# STM32F413CG_WM8731.net
KiCad netlist of a schematic drawn in EAGLE
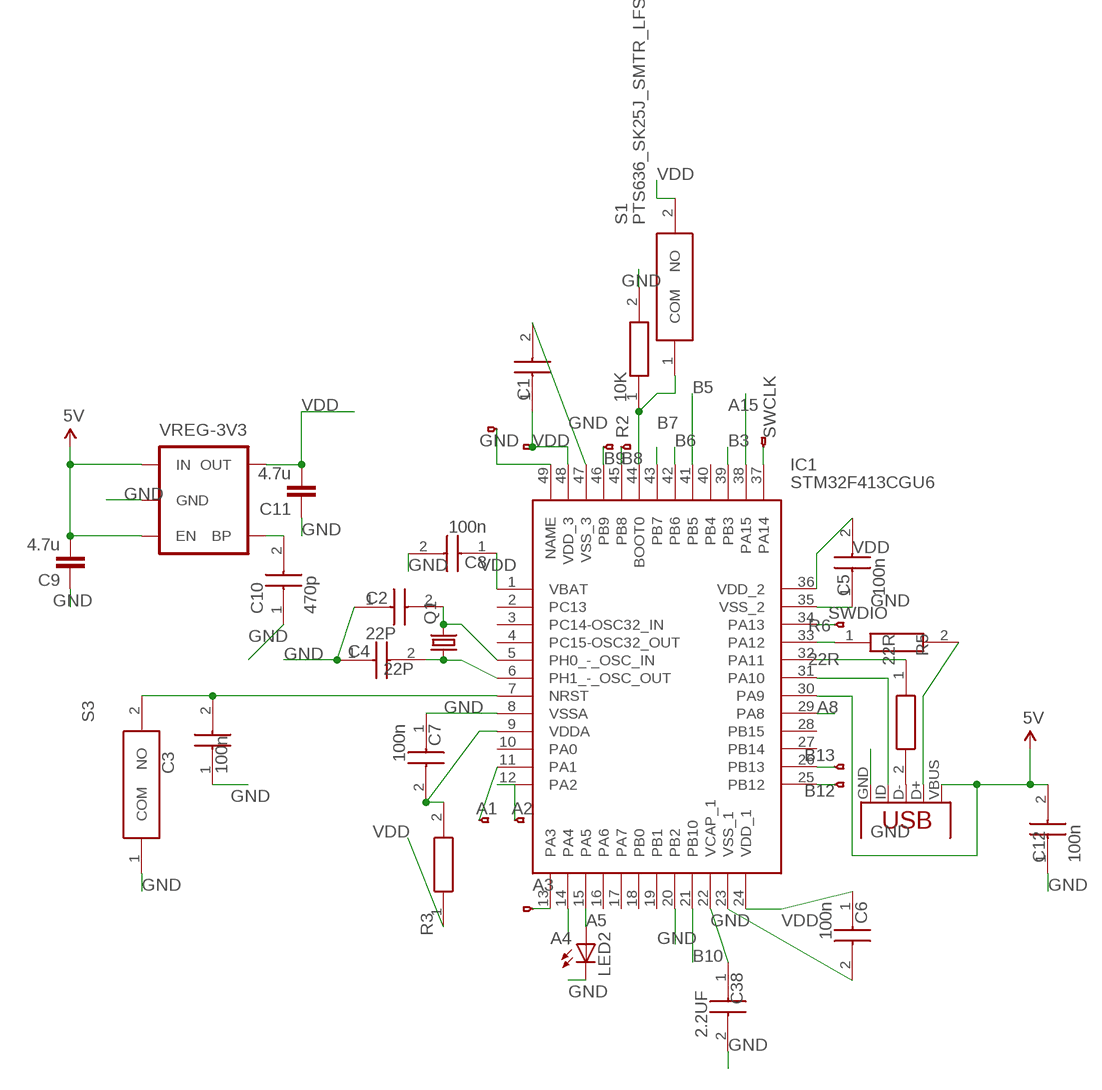
[diagram p0: schematic, sheet 1]
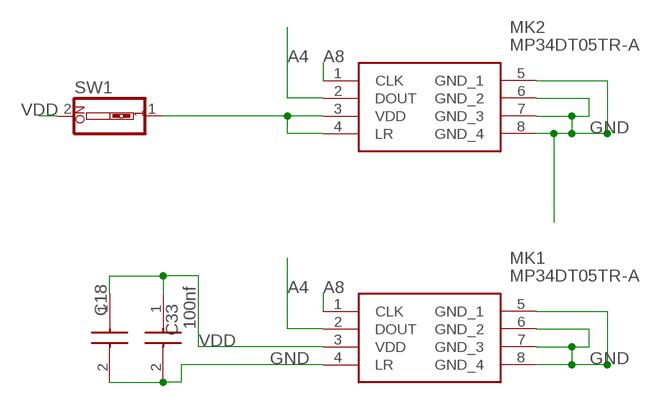
[diagram p1: schematic, sheet 2]
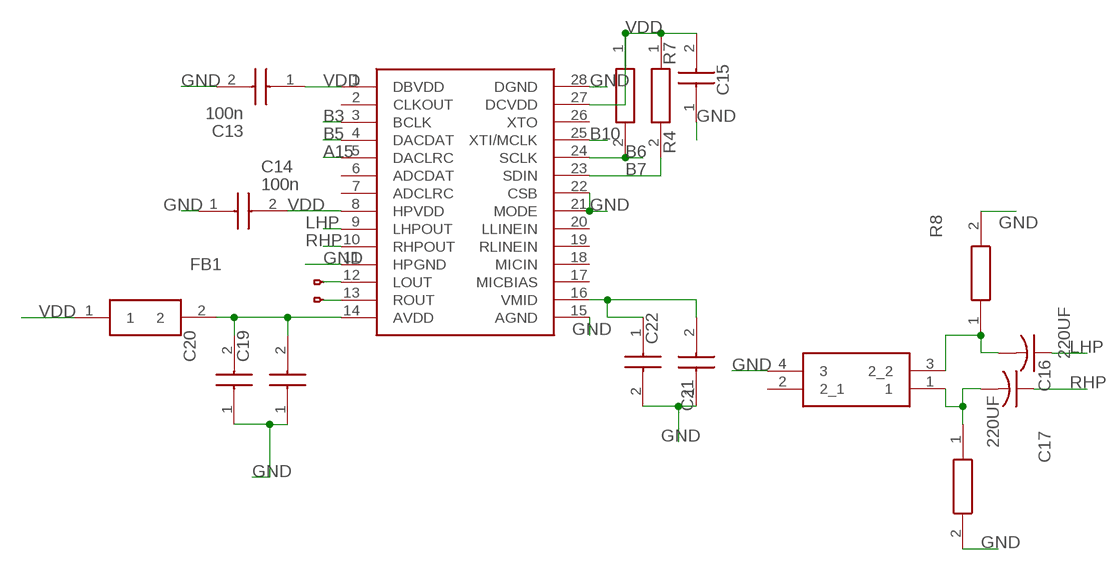
[diagram p2: schematic, sheet 3]

(export (version "E")
  (design (tool "Eeschema 10.0.6"))
  (components
    (comp (ref "C13")
      (value "100n")
      (footprint "eagle-import:CAPC1608X95N")
      (fields
        (field (name "MANUFACTURER_PART_NUMBER") "C0603C104M4RAC7411")
        (field (name "MOUSER_PART_NUMBER") "80-C0603C104M4R7411")
      )
      (libsource (lib "eagle-import") (part "C0603C104M4RAC7411"))
    )
    (comp (ref "C14")
      (value "100n")
      (footprint "eagle-import:CAPC1608X95N")
      (fields
        (field (name "MANUFACTURER_PART_NUMBER") "C0603C104M4RAC7411")
        (field (name "MOUSER_PART_NUMBER") "80-C0603C104M4R7411")
      )
      (libsource (lib "eagle-import") (part "C0603C104M4RAC7411"))
    )
    (comp (ref "C15")
      (value "C0603C104M4RAC7411")
      (footprint "eagle-import:CAPC1608X95N")
      (fields (field (name "MOUSER_PART_NUMBER") "80-C0603C104M4R7411"))
      (libsource (lib "eagle-import") (part "C0603C104M4RAC7411"))
    )
    (comp (ref "C16")
      (value "220UF")
      (footprint "eagle-import:C025-024X044")
      (libsource (lib "eagle-import") (part "C-US025-024X044"))
    )
    (comp (ref "C17")
      (value "220UF")
      (footprint "eagle-import:C025-024X044")
      (libsource (lib "eagle-import") (part "C-US025-024X044"))
    )
    (comp (ref "C19")
      (value "C0603C104M4RAC7411")
      (footprint "eagle-import:CAPC1608X95N")
      (fields (field (name "MOUSER_PART_NUMBER") "80-C0603C104M4R7411"))
      (libsource (lib "eagle-import") (part "C0603C104M4RAC7411_100nF_C0603C104M4RAC7411"))
    )
    (comp (ref "C20")
      (value "CL21A106KAYNNNE_10UF")
      (footprint "eagle-import:CAPC2012X145N")
      (fields (field (name "MANUFACTURER_PART_NUMBER") "CL21A106KAYNNNE"))
      (libsource (lib "eagle-import") (part "CL21A106KAYNNNE"))
    )
    (comp (ref "C21")
      (value "CL21A106KAYNNNE")
      (footprint "eagle-import:CAPC2012X145N")
      (libsource (lib "eagle-import") (part "CL21A106KAYNNNE"))
    )
    (comp (ref "C22")
      (value "C0603C104M4RAC7411")
      (footprint "eagle-import:CAPC1608X95N")
      (fields (field (name "MOUSER_PART_NUMBER") "80-C0603C104M4R7411"))
      (libsource (lib "eagle-import") (part "C0603C104M4RAC7411_100nF_C0603C104M4RAC7411"))
    )
    (comp (ref "FB1")
      (value "BLM18BD252SN1D")
      (footprint "eagle-import:BEADC1608X95N")
      (fields
        (field (name "MOUSER_PART_NUMBER") "81-BLM18BD252SN1D")
        (field (name "RS_PART_NUMBER") "7241321P")
      )
      (libsource (lib "eagle-import") (part "BLM18BD252SN1D"))
    )
    (comp (ref "IC2")
      (value "WM8731SEDS_RV")
      (footprint "eagle-import:SOP65P780X200-28N")
      (fields (field (name "MANUFACTURER_PART_NUMBER") "WM8731SEDS/RV"))
      (libsource (lib "eagle-import") (part "WM8731SEDS_RV"))
    )
    (comp (ref "J2")
      (value "1503_02")
      (footprint "eagle-import:150302")
      (fields (field (name "MANUFACTURER_PART_NUMBER") "1503 02"))
      (libsource (lib "eagle-import") (part "1503_02"))
    )
    (comp (ref "JP12")
      (value "HEADERHOLE-HEADERHOLE")
      (footprint "eagle-import:1X1-HEADER-HOLE")
      (libsource (lib "eagle-import") (part "HEADERHOLE-HEADERHOLE"))
    )
    (comp (ref "JP13")
      (value "HEADERHOLE-HEADERHOLE")
      (footprint "eagle-import:1X1-HEADER-HOLE")
      (libsource (lib "eagle-import") (part "HEADERHOLE-HEADERHOLE"))
    )
    (comp (ref "R4")
      (value "CR0603-JW-472ELF")
      (footprint "eagle-import:RESC1608X55N")
      (fields
        (field (name "MOUSER_PART_NUMBER") "652-CR0603-JW-472ELF")
        (field (name "RS_PART_NUMBER") "7408956P")
      )
      (libsource (lib "eagle-import") (part "CR0603-JW-472ELF"))
    )
    (comp (ref "R7")
      (value "CR0603-JW-472ELF")
      (footprint "eagle-import:RESC1608X55N")
      (fields
        (field (name "MOUSER_PART_NUMBER") "652-CR0603-JW-472ELF")
        (field (name "RS_PART_NUMBER") "7408956P")
      )
      (libsource (lib "eagle-import") (part "CR0603-JW-472ELF"))
    )
    (comp (ref "R8")
      (value "CR0603-JW-472ELF")
      (footprint "eagle-import:RESC1608X55N")
      (fields
        (field (name "MOUSER_PART_NUMBER") "652-CR0603-JW-472ELF")
        (field (name "RS_PART_NUMBER") "7408956P")
      )
      (libsource (lib "eagle-import") (part "CR0603-JW-472ELF"))
    )
    (comp (ref "R9")
      (value "CR0603-JW-472ELF")
      (footprint "eagle-import:RESC1608X55N")
      (fields
        (field (name "MOUSER_PART_NUMBER") "652-CR0603-JW-472ELF")
        (field (name "RS_PART_NUMBER") "7408956P")
      )
      (libsource (lib "eagle-import") (part "CR0603-JW-472ELF"))
    )
    (comp (ref "C1")
      (value "C0603C104M4RAC7411")
      (footprint "eagle-import:CAPC1608X95N")
      (fields (field (name "MOUSER_PART_NUMBER") "80-C0603C104M4R7411"))
      (libsource (lib "eagle-import") (part "C0603C104M4RAC7411"))
    )
    (comp (ref "C2")
      (value "22P")
      (footprint "eagle-import:CAPC1608X80N")
      (fields
        (field (name "MANUFACTURER_PART_NUMBER") "C1608C0G1H150J080AA")
        (field (name "MOUSER_PART_NUMBER") "810-C1608C0G1H150J")
        (field (name "RS_PART_NUMBER") "7882935")
      )
      (libsource (lib "eagle-import") (part "C1608C0G1H150J080AA"))
    )
    (comp (ref "C3")
      (value "100n")
      (footprint "eagle-import:CAPC1608X95N")
      (fields
        (field (name "MANUFACTURER_PART_NUMBER") "C0603C104M4RAC7411")
        (field (name "MOUSER_PART_NUMBER") "80-C0603C104M4R7411")
      )
      (libsource (lib "eagle-import") (part "C0603C104M4RAC7411"))
    )
    (comp (ref "C4")
      (value "22P")
      (footprint "eagle-import:CAPC1608X80N")
      (fields
        (field (name "MANUFACTURER_PART_NUMBER") "C1608C0G1H150J080AA")
        (field (name "MOUSER_PART_NUMBER") "810-C1608C0G1H150J")
        (field (name "RS_PART_NUMBER") "7882935")
      )
      (libsource (lib "eagle-import") (part "C1608C0G1H150J080AA"))
    )
    (comp (ref "C5")
      (value "100n")
      (footprint "eagle-import:CAPC1608X95N")
      (fields
        (field (name "MANUFACTURER_PART_NUMBER") "C0603C104M4RAC7411")
        (field (name "MOUSER_PART_NUMBER") "80-C0603C104M4R7411")
      )
      (libsource (lib "eagle-import") (part "C0603C104M4RAC7411"))
    )
    (comp (ref "C6")
      (value "100n")
      (footprint "eagle-import:CAPC1608X95N")
      (fields
        (field (name "MANUFACTURER_PART_NUMBER") "C0603C104M4RAC7411")
        (field (name "MOUSER_PART_NUMBER") "80-C0603C104M4R7411")
      )
      (libsource (lib "eagle-import") (part "C0603C104M4RAC7411"))
    )
    (comp (ref "C7")
      (value "100n")
      (footprint "eagle-import:CAPC1608X95N")
      (fields
        (field (name "MANUFACTURER_PART_NUMBER") "C0603C104M4RAC7411")
        (field (name "MOUSER_PART_NUMBER") "80-C0603C104M4R7411")
      )
      (libsource (lib "eagle-import") (part "C0603C104M4RAC7411"))
    )
    (comp (ref "C8")
      (value "100n")
      (footprint "eagle-import:CAPC1608X95N")
      (fields
        (field (name "MANUFACTURER_PART_NUMBER") "C0603C104M4RAC7411")
        (field (name "MOUSER_PART_NUMBER") "80-C0603C104M4R7411")
      )
      (libsource (lib "eagle-import") (part "C0603C104M4RAC7411"))
    )
    (comp (ref "C9")
      (value "4.7u")
      (footprint "eagle-import:C2.5-3")
      (libsource (lib "eagle-import") (part "C2,5-3"))
    )
    (comp (ref "C10")
      (value "470p")
      (footprint "eagle-import:CAPC1608X87N")
      (fields
        (field (name "MANUFACTURER_PART_NUMBER") "C0603C471K3RACTU")
        (field (name "MOUSER_PART_NUMBER") "80-C0603C471K3R")
      )
      (libsource (lib "eagle-import") (part "C0603C471K3RACTU"))
    )
    (comp (ref "C11")
      (value "4.7u")
      (footprint "eagle-import:C2.5-3")
      (libsource (lib "eagle-import") (part "C2,5-3"))
    )
    (comp (ref "C12")
      (value "100n")
      (footprint "eagle-import:CAPC1608X95N")
      (fields
        (field (name "MANUFACTURER_PART_NUMBER") "C0603C104M4RAC7411")
        (field (name "MOUSER_PART_NUMBER") "80-C0603C104M4R7411")
      )
      (libsource (lib "eagle-import") (part "C0603C104M4RAC7411"))
    )
    (comp (ref "C38")
      (value "2.2UF")
      (footprint "eagle-import:CAPC2012X145N")
      (fields
        (field (name "MANUFACTURER_PART_NUMBER") "C2012X7R1E225K125AB")
        (field (name "MOUSER_PART_NUMBER") "810-C2012X7R1E225K")
        (field (name "RS_PART_NUMBER") "9159394P")
      )
      (libsource (lib "eagle-import") (part "C2012X7R1E225K125AB"))
    )
    (comp (ref "IC1")
      (value "STM32F413CGU6")
      (footprint "eagle-import:QFN50P700X700X60-49N")
      (fields (field (name "MOUSER_PART_NUMBER") "511-STM32F413CGU6"))
      (libsource (lib "eagle-import") (part "STM32F413CGU6"))
    )
    (comp (ref "JP1")
      (value "HEADERHOLE-HEADERHOLE")
      (footprint "eagle-import:1X1-HEADER-HOLE")
      (libsource (lib "eagle-import") (part "HEADERHOLE-HEADERHOLE"))
    )
    (comp (ref "JP2")
      (value "HEADERHOLE-HEADERHOLE")
      (footprint "eagle-import:1X1-HEADER-HOLE")
      (libsource (lib "eagle-import") (part "HEADERHOLE-HEADERHOLE"))
    )
    (comp (ref "JP3")
      (value "HEADERHOLE-HEADERHOLE")
      (footprint "eagle-import:1X1-HEADER-HOLE")
      (libsource (lib "eagle-import") (part "HEADERHOLE-HEADERHOLE"))
    )
    (comp (ref "JP4")
      (value "HEADERHOLE-HEADERHOLE")
      (footprint "eagle-import:1X1-HEADER-HOLE")
      (libsource (lib "eagle-import") (part "HEADERHOLE-HEADERHOLE"))
    )
    (comp (ref "JP5")
      (value "HEADERHOLE-HEADERHOLE")
      (footprint "eagle-import:1X1-HEADER-HOLE")
      (libsource (lib "eagle-import") (part "HEADERHOLE-HEADERHOLE"))
    )
    (comp (ref "JP6")
      (value "HEADERHOLE-HEADERHOLE")
      (footprint "eagle-import:1X1-HEADER-HOLE")
      (libsource (lib "eagle-import") (part "HEADERHOLE-HEADERHOLE"))
    )
    (comp (ref "JP7")
      (value "HEADERHOLE-HEADERHOLE")
      (footprint "eagle-import:1X1-HEADER-HOLE")
      (libsource (lib "eagle-import") (part "HEADERHOLE-HEADERHOLE"))
    )
    (comp (ref "JP8")
      (value "HEADERHOLE-HEADERHOLE")
      (footprint "eagle-import:1X1-HEADER-HOLE")
      (libsource (lib "eagle-import") (part "HEADERHOLE-HEADERHOLE"))
    )
    (comp (ref "JP9")
      (value "HEADERHOLE-HEADERHOLE")
      (footprint "eagle-import:1X1-HEADER-HOLE")
      (libsource (lib "eagle-import") (part "HEADERHOLE-HEADERHOLE"))
    )
    (comp (ref "JP10")
      (value "HEADERHOLE-HEADERHOLE")
      (footprint "eagle-import:1X1-HEADER-HOLE")
      (libsource (lib "eagle-import") (part "HEADERHOLE-HEADERHOLE"))
    )
    (comp (ref "JP11")
      (value "HEADERHOLE-HEADERHOLE")
      (footprint "eagle-import:1X1-HEADER-HOLE")
      (libsource (lib "eagle-import") (part "HEADERHOLE-HEADERHOLE"))
    )
    (comp (ref "LED2")
      (value "LED0603")
      (footprint "eagle-import:LED-0603")
      (libsource (lib "eagle-import") (part "LED0603"))
    )
    (comp (ref "Q1")
      (value "CRYSTALHC49S")
      (footprint "eagle-import:HC49_S")
      (libsource (lib "eagle-import") (part "CRYSTALHC49S"))
    )
    (comp (ref "R2")
      (value "10K")
      (footprint "eagle-import:RESC1005X40N")
      (fields
        (field (name "MANUFACTURER_PART_NUMBER") "CRCW040210K0JNED")
        (field (name "MOUSER_PART_NUMBER") "71-CRCW0402J-10K-E3")
      )
      (libsource (lib "eagle-import") (part "CRCW040210K0JNED"))
    )
    (comp (ref "R3")
      (value "CRCW040222R0FKED")
      (footprint "eagle-import:RESC1005X40N")
      (fields
        (field (name "MOUSER_PART_NUMBER") "71-CRCW0402-22-E3")
        (field (name "RS_PART_NUMBER") "6788983P")
      )
      (libsource (lib "eagle-import") (part "CRCW040222R0FKED"))
    )
    (comp (ref "R5")
      (value "22R")
      (footprint "eagle-import:RESC1005X40N")
      (fields
        (field (name "MANUFACTURER_PART_NUMBER") "CRCW040222R0FKED")
        (field (name "MOUSER_PART_NUMBER") "71-CRCW0402-22-E3")
        (field (name "RS_PART_NUMBER") "6788983P")
      )
      (libsource (lib "eagle-import") (part "CRCW040222R0FKED"))
    )
    (comp (ref "R6")
      (value "22R")
      (footprint "eagle-import:RESC1005X40N")
      (fields
        (field (name "MANUFACTURER_PART_NUMBER") "CRCW040222R0FKED")
        (field (name "MOUSER_PART_NUMBER") "71-CRCW0402-22-E3")
        (field (name "RS_PART_NUMBER") "6788983P")
      )
      (libsource (lib "eagle-import") (part "CRCW040222R0FKED"))
    )
    (comp (ref "S1")
      (value "PTS636_SK25J_SMTR_LFS")
      (footprint "eagle-import:PTS636SK25JSMTRLFS")
      (fields
        (field (name "MANUFACTURER_PART_NUMBER") "PTS636 SK25J SMTR LFS")
        (field (name "MOUSER_PART_NUMBER") "611-PTS636SK25JSMTRL")
      )
      (libsource (lib "eagle-import") (part "PTS636_SK25J_SMTR_LFS"))
    )
    (comp (ref "S3")
      (value "PTS636_SK25J_SMTR_LFS")
      (footprint "eagle-import:PTS636SK25JSMTRLFS")
      (fields
        (field (name "MANUFACTURER_PART_NUMBER") "PTS636 SK25J SMTR LFS")
        (field (name "MOUSER_PART_NUMBER") "611-PTS636SK25JSMTRL")
      )
      (libsource (lib "eagle-import") (part "PTS636_SK25J_SMTR_LFS"))
    )
    (comp (ref "VREG-3V3")
      (value "V_REG_LDOSMD")
      (footprint "eagle-import:SOT23-5")
      (libsource (lib "eagle-import") (part "V_REG_LDOSMD"))
    )
    (comp (ref "X1")
      (value "USB-MICROB-SMD")
      (footprint "eagle-import:USB-MICROB-SMD")
      (libsource (lib "eagle-import") (part "USB-MICROB-SMD"))
    )
    (comp (ref "C18")
      (value "1UF")
      (footprint "eagle-import:CAPC1005X55N")
      (fields
        (field (name "MANUFACTURER_PART_NUMBER") "CC0402KRX5R6BB105")
        (field (name "MOUSER_PART_NUMBER") "603-CC402KRX5R6BB105")
      )
      (libsource (lib "eagle-import") (part "CC0402KRX5R6BB105"))
    )
    (comp (ref "C33")
      (value "100nf")
      (footprint "eagle-import:CAPC1608X95N")
      (fields
        (field (name "MANUFACTURER_PART_NUMBER") "C0603C104M4RAC7411")
        (field (name "MOUSER_PART_NUMBER") "80-C0603C104M4R7411")
      )
      (libsource (lib "eagle-import") (part "C0603C104M4RAC7411"))
    )
    (comp (ref "MK1")
      (value "MP34DT05TR-A")
      (footprint "eagle-import:MP34DT05TRA")
      (fields (field (name "MOUSER_PART_NUMBER") "511-MP34DT05TR-A"))
      (libsource (lib "eagle-import") (part "MP34DT05TR-A"))
    )
    (comp (ref "MK2")
      (value "MP34DT05TR-A")
      (footprint "eagle-import:MP34DT05TRA")
      (fields (field (name "MOUSER_PART_NUMBER") "511-MP34DT05TR-A"))
      (libsource (lib "eagle-import") (part "MP34DT05TR-A"))
    )
    (comp (ref "SW1")
      (value "SW_DIP-1")
      (footprint "eagle-import:EDG-01")
      (libsource (lib "eagle-import") (part "SW_DIP-1"))
    )
  )
  (nets
    (net (code "1") (name "5V") (class "Default")
      (node (ref "C12") (pin "2") (pinfunction "2_2") (pintype "bidirectional"))
      (node (ref "C9") (pin "2") (pinfunction "2_2") (pintype "passive"))
      (node (ref "IC1") (pin "30") (pinfunction "PA9_30") (pintype "bidirectional"))
      (node (ref "VREG-3V3") (pin "1") (pinfunction "IN_1") (pintype "input"))
      (node (ref "VREG-3V3") (pin "3") (pinfunction "EN_3") (pintype "input"))
      (node (ref "X1") (pin "VBUS") (pinfunction "VBUS_VBUS") (pintype "bidirectional"))
    )
    (net (code "2") (name "A1") (class "Default")
      (node (ref "IC1") (pin "11") (pinfunction "PA1_11") (pintype "bidirectional"))
      (node (ref "JP8") (pin "1") (pinfunction "P$1_1") (pintype "bidirectional"))
    )
    (net (code "3") (name "A2") (class "Default")
      (node (ref "IC1") (pin "12") (pinfunction "PA2_12") (pintype "bidirectional"))
      (node (ref "JP9") (pin "1") (pinfunction "P$1_1") (pintype "bidirectional"))
    )
    (net (code "4") (name "A3") (class "Default")
      (node (ref "IC1") (pin "13") (pinfunction "PA3_13") (pintype "bidirectional"))
      (node (ref "JP10") (pin "1") (pinfunction "P$1_1") (pintype "bidirectional"))
    )
    (net (code "5") (name "A4") (class "Default")
      (node (ref "IC1") (pin "14") (pinfunction "PA4_14") (pintype "bidirectional"))
      (node (ref "MK1") (pin "2") (pinfunction "DOUT_2") (pintype "bidirectional"))
      (node (ref "MK2") (pin "2") (pinfunction "DOUT_2") (pintype "bidirectional"))
    )
    (net (code "6") (name "A5") (class "Default")
      (node (ref "IC1") (pin "15") (pinfunction "PA5_15") (pintype "bidirectional"))
      (node (ref "LED2") (pin "A") (pinfunction "A_A") (pintype "passive"))
    )
    (net (code "7") (name "A8") (class "Default")
      (node (ref "IC1") (pin "29") (pinfunction "PA8_29") (pintype "bidirectional"))
      (node (ref "MK1") (pin "1") (pinfunction "CLK_1") (pintype "bidirectional"))
      (node (ref "MK2") (pin "1") (pinfunction "CLK_1") (pintype "bidirectional"))
    )
    (net (code "8") (name "A15") (class "Default")
      (node (ref "IC1") (pin "38") (pinfunction "PA15_38") (pintype "bidirectional"))
      (node (ref "IC2") (pin "5") (pinfunction "DACLRC_5") (pintype "bidirectional"))
    )
    (net (code "9") (name "B3") (class "Default")
      (node (ref "IC1") (pin "39") (pinfunction "PB3_39") (pintype "bidirectional"))
      (node (ref "IC2") (pin "3") (pinfunction "BCLK_3") (pintype "bidirectional"))
    )
    (net (code "10") (name "B5") (class "Default")
      (node (ref "IC1") (pin "41") (pinfunction "PB5_41") (pintype "bidirectional"))
      (node (ref "IC2") (pin "4") (pinfunction "DACDAT_4") (pintype "bidirectional"))
    )
    (net (code "11") (name "B6") (class "Default")
      (node (ref "IC1") (pin "42") (pinfunction "PB6_42") (pintype "bidirectional"))
      (node (ref "IC2") (pin "24") (pinfunction "SCLK_24") (pintype "bidirectional"))
      (node (ref "R4") (pin "2") (pinfunction "2_2") (pintype "bidirectional"))
    )
    (net (code "12") (name "B7") (class "Default")
      (node (ref "IC1") (pin "43") (pinfunction "PB7_43") (pintype "bidirectional"))
      (node (ref "IC2") (pin "23") (pinfunction "SDIN_23") (pintype "bidirectional"))
      (node (ref "R7") (pin "2") (pinfunction "2_2") (pintype "bidirectional"))
    )
    (net (code "13") (name "B8") (class "Default")
      (node (ref "IC1") (pin "45") (pinfunction "PB8_45") (pintype "bidirectional"))
      (node (ref "JP5") (pin "1") (pinfunction "P$1_1") (pintype "bidirectional"))
    )
    (net (code "14") (name "B9") (class "Default")
      (node (ref "IC1") (pin "46") (pinfunction "PB9_46") (pintype "bidirectional"))
      (node (ref "JP11") (pin "1") (pinfunction "P$1_1") (pintype "bidirectional"))
    )
    (net (code "15") (name "B10") (class "Default")
      (node (ref "IC1") (pin "21") (pinfunction "PB10_21") (pintype "bidirectional"))
      (node (ref "IC2") (pin "25") (pinfunction "XTI/MCLK_25") (pintype "bidirectional"))
    )
    (net (code "16") (name "B12") (class "Default")
      (node (ref "IC1") (pin "25") (pinfunction "PB12_25") (pintype "bidirectional"))
      (node (ref "JP7") (pin "1") (pinfunction "P$1_1") (pintype "bidirectional"))
    )
    (net (code "17") (name "B13") (class "Default")
      (node (ref "IC1") (pin "26") (pinfunction "PB13_26") (pintype "bidirectional"))
      (node (ref "JP6") (pin "1") (pinfunction "P$1_1") (pintype "bidirectional"))
    )
    (net (code "18") (name "GND") (class "Default")
      (node (ref "C1") (pin "2") (pinfunction "2_2") (pintype "bidirectional"))
      (node (ref "C10") (pin "1") (pinfunction "1_1") (pintype "bidirectional"))
      (node (ref "C11") (pin "1") (pinfunction "1_1") (pintype "passive"))
      (node (ref "C12") (pin "1") (pinfunction "1_1") (pintype "bidirectional"))
      (node (ref "C13") (pin "2") (pinfunction "2_2") (pintype "bidirectional"))
      (node (ref "C14") (pin "1") (pinfunction "1_1") (pintype "bidirectional"))
      (node (ref "C15") (pin "1") (pinfunction "1_1") (pintype "bidirectional"))
      (node (ref "C18") (pin "2") (pinfunction "C2_2") (pintype "bidirectional"))
      (node (ref "C19") (pin "1") (pinfunction "1_1") (pintype "bidirectional"))
      (node (ref "C2") (pin "1") (pinfunction "1_1") (pintype "bidirectional"))
      (node (ref "C20") (pin "1") (pinfunction "1_1") (pintype "bidirectional"))
      (node (ref "C21") (pin "2") (pinfunction "2_2") (pintype "bidirectional"))
      (node (ref "C22") (pin "1") (pinfunction "1_1") (pintype "bidirectional"))
      (node (ref "C3") (pin "1") (pinfunction "1_1") (pintype "bidirectional"))
      (node (ref "C33") (pin "2") (pinfunction "2_2") (pintype "bidirectional"))
      (node (ref "C38") (pin "2") (pinfunction "2_2") (pintype "bidirectional"))
      (node (ref "C4") (pin "1") (pinfunction "1_1") (pintype "bidirectional"))
      (node (ref "C5") (pin "1") (pinfunction "1_1") (pintype "bidirectional"))
      (node (ref "C6") (pin "2") (pinfunction "2_2") (pintype "bidirectional"))
      (node (ref "C7") (pin "1") (pinfunction "1_1") (pintype "bidirectional"))
      (node (ref "C8") (pin "2") (pinfunction "2_2") (pintype "bidirectional"))
      (node (ref "C9") (pin "1") (pinfunction "1_1") (pintype "passive"))
      (node (ref "IC1") (pin "20") (pinfunction "PB2_20") (pintype "bidirectional"))
      (node (ref "IC1") (pin "23") (pinfunction "VSS_1_23") (pintype "power_in"))
      (node (ref "IC1") (pin "35") (pinfunction "VSS_2_35") (pintype "power_in"))
      (node (ref "IC1") (pin "47") (pinfunction "VSS_3_47") (pintype "power_in"))
      (node (ref "IC1") (pin "49") (pinfunction "NAME_49") (pintype "bidirectional"))
      (node (ref "IC1") (pin "8") (pinfunction "VSSA_8") (pintype "power_in"))
      (node (ref "IC2") (pin "11") (pinfunction "HPGND_11") (pintype "bidirectional"))
      (node (ref "IC2") (pin "15") (pinfunction "AGND_15") (pintype "bidirectional"))
      (node (ref "IC2") (pin "21") (pinfunction "MODE_21") (pintype "bidirectional"))
      (node (ref "IC2") (pin "22") (pinfunction "CSB_22") (pintype "bidirectional"))
      (node (ref "IC2") (pin "28") (pinfunction "DGND_28") (pintype "bidirectional"))
      (node (ref "J2") (pin "4") (pinfunction "3_4") (pintype "bidirectional"))
      (node (ref "JP1") (pin "1") (pinfunction "P$1_1") (pintype "bidirectional"))
      (node (ref "LED2") (pin "C") (pinfunction "C_C") (pintype "passive"))
      (node (ref "MK1") (pin "4") (pinfunction "LR_4") (pintype "bidirectional"))
      (node (ref "MK1") (pin "5") (pinfunction "GND_1_5") (pintype "bidirectional"))
      (node (ref "MK1") (pin "6") (pinfunction "GND_2_6") (pintype "bidirectional"))
      (node (ref "MK1") (pin "7") (pinfunction "GND_3_7") (pintype "bidirectional"))
      (node (ref "MK1") (pin "8") (pinfunction "GND_4_8") (pintype "bidirectional"))
      (node (ref "MK2") (pin "5") (pinfunction "GND_1_5") (pintype "bidirectional"))
      (node (ref "MK2") (pin "6") (pinfunction "GND_2_6") (pintype "bidirectional"))
      (node (ref "MK2") (pin "7") (pinfunction "GND_3_7") (pintype "bidirectional"))
      (node (ref "MK2") (pin "8") (pinfunction "GND_4_8") (pintype "bidirectional"))
      (node (ref "R2") (pin "2") (pinfunction "2_2") (pintype "bidirectional"))
      (node (ref "R8") (pin "2") (pinfunction "2_2") (pintype "bidirectional"))
      (node (ref "R9") (pin "2") (pinfunction "2_2") (pintype "bidirectional"))
      (node (ref "S3") (pin "1") (pinfunction "COM_1") (pintype "bidirectional"))
      (node (ref "VREG-3V3") (pin "2") (pinfunction "GND_2") (pintype "input"))
      (node (ref "X1") (pin "GND") (pinfunction "GND_GND") (pintype "bidirectional"))
    )
    (net (code "19") (name "LHP") (class "Default")
      (node (ref "C16") (pin "1") (pinfunction "1_1") (pintype "passive"))
      (node (ref "IC2") (pin "9") (pinfunction "LHPOUT_9") (pintype "bidirectional"))
    )
    (net (code "20") (name "Net-(C17-Pad2)") (class "Default")
      (node (ref "C17") (pin "2") (pinfunction "2_2") (pintype "passive"))
      (node (ref "J2") (pin "1") (pinfunction "1_1") (pintype "bidirectional"))
      (node (ref "R9") (pin "1") (pinfunction "1_1") (pintype "bidirectional"))
    )
    (net (code "21") (name "Net-(IC1-BOOT0)") (class "Default")
      (node (ref "IC1") (pin "44") (pinfunction "BOOT0_44") (pintype "bidirectional"))
      (node (ref "R2") (pin "1") (pinfunction "1_1") (pintype "bidirectional"))
      (node (ref "S1") (pin "1") (pinfunction "COM_1") (pintype "bidirectional"))
    )
    (net (code "22") (name "Net-(IC1-NRST)") (class "Default")
      (node (ref "C3") (pin "2") (pinfunction "2_2") (pintype "bidirectional"))
      (node (ref "IC1") (pin "7") (pinfunction "NRST_7") (pintype "bidirectional"))
      (node (ref "S3") (pin "2") (pinfunction "NO_2") (pintype "bidirectional"))
    )
    (net (code "23") (name "Net-(IC1-PA10)") (class "Default")
      (node (ref "IC1") (pin "31") (pinfunction "PA10_31") (pintype "bidirectional"))
      (node (ref "X1") (pin "ID") (pinfunction "ID_ID") (pintype "bidirectional"))
    )
    (net (code "24") (name "Net-(IC1-PA11)") (class "Default")
      (node (ref "IC1") (pin "32") (pinfunction "PA11_32") (pintype "bidirectional"))
      (node (ref "R5") (pin "1") (pinfunction "1_1") (pintype "bidirectional"))
    )
    (net (code "25") (name "Net-(IC1-PA12)") (class "Default")
      (node (ref "IC1") (pin "33") (pinfunction "PA12_33") (pintype "bidirectional"))
      (node (ref "R6") (pin "1") (pinfunction "1_1") (pintype "bidirectional"))
    )
    (net (code "26") (name "Net-(IC1-PH0_-_OSC_IN)") (class "Default")
      (node (ref "C2") (pin "2") (pinfunction "2_2") (pintype "bidirectional"))
      (node (ref "IC1") (pin "5") (pinfunction "PH0_-_OSC_IN_5") (pintype "bidirectional"))
      (node (ref "Q1") (pin "2") (pinfunction "2_2") (pintype "passive"))
    )
    (net (code "27") (name "Net-(IC1-PH1_-_OSC_OUT)") (class "Default")
      (node (ref "C4") (pin "2") (pinfunction "2_2") (pintype "bidirectional"))
      (node (ref "IC1") (pin "6") (pinfunction "PH1_-_OSC_OUT_6") (pintype "bidirectional"))
      (node (ref "Q1") (pin "1") (pinfunction "1_1") (pintype "passive"))
    )
    (net (code "28") (name "Net-(IC1-VCAP_1)") (class "Default")
      (node (ref "C38") (pin "1") (pinfunction "1_1") (pintype "bidirectional"))
      (node (ref "IC1") (pin "22") (pinfunction "VCAP_1_22") (pintype "power_in"))
    )
    (net (code "29") (name "Net-(IC1-VDDA)") (class "Default")
      (node (ref "C7") (pin "2") (pinfunction "2_2") (pintype "bidirectional"))
      (node (ref "IC1") (pin "9") (pinfunction "VDDA_9") (pintype "power_in"))
      (node (ref "R3") (pin "2") (pinfunction "2_2") (pintype "bidirectional"))
    )
    (net (code "30") (name "Net-(IC2-AVDD)") (class "Default")
      (node (ref "C19") (pin "2") (pinfunction "2_2") (pintype "bidirectional"))
      (node (ref "C20") (pin "2") (pinfunction "2_2") (pintype "bidirectional"))
      (node (ref "FB1") (pin "2") (pinfunction "2_2") (pintype "bidirectional"))
      (node (ref "IC2") (pin "14") (pinfunction "AVDD_14") (pintype "bidirectional"))
    )
    (net (code "31") (name "Net-(IC2-LOUT)") (class "Default")
      (node (ref "IC2") (pin "12") (pinfunction "LOUT_12") (pintype "bidirectional"))
      (node (ref "JP13") (pin "1") (pinfunction "P$1_1") (pintype "bidirectional"))
    )
    (net (code "32") (name "Net-(IC2-ROUT)") (class "Default")
      (node (ref "IC2") (pin "13") (pinfunction "ROUT_13") (pintype "bidirectional"))
      (node (ref "JP12") (pin "1") (pinfunction "P$1_1") (pintype "bidirectional"))
    )
    (net (code "33") (name "Net-(IC2-VMID)") (class "Default")
      (node (ref "C21") (pin "1") (pinfunction "1_1") (pintype "bidirectional"))
      (node (ref "C22") (pin "2") (pinfunction "2_2") (pintype "bidirectional"))
      (node (ref "IC2") (pin "16") (pinfunction "VMID_16") (pintype "bidirectional"))
    )
    (net (code "34") (name "Net-(J2-2_2)") (class "Default")
      (node (ref "C16") (pin "2") (pinfunction "2_2") (pintype "passive"))
      (node (ref "J2") (pin "3") (pinfunction "2_2_3") (pintype "bidirectional"))
      (node (ref "R8") (pin "1") (pinfunction "1_1") (pintype "bidirectional"))
    )
    (net (code "35") (name "Net-(MK2-LR)") (class "Default")
      (node (ref "MK2") (pin "3") (pinfunction "VDD_3") (pintype "bidirectional"))
      (node (ref "MK2") (pin "4") (pinfunction "LR_4") (pintype "bidirectional"))
      (node (ref "SW1") (pin "1") (pinfunction "1_1") (pintype "passive"))
    )
    (net (code "36") (name "Net-(R5-Pad2)") (class "Default")
      (node (ref "R5") (pin "2") (pinfunction "2_2") (pintype "bidirectional"))
      (node (ref "X1") (pin "D-") (pinfunction "D-_D-") (pintype "bidirectional"))
    )
    (net (code "37") (name "Net-(R6-Pad2)") (class "Default")
      (node (ref "R6") (pin "2") (pinfunction "2_2") (pintype "bidirectional"))
      (node (ref "X1") (pin "D+") (pinfunction "D+_D+") (pintype "bidirectional"))
    )
    (net (code "38") (name "Net-(VREG-3V3-BP)") (class "Default")
      (node (ref "C10") (pin "2") (pinfunction "2_2") (pintype "bidirectional"))
      (node (ref "VREG-3V3") (pin "4") (pinfunction "BP_4") (pintype "input"))
    )
    (net (code "39") (name "RHP") (class "Default")
      (node (ref "C17") (pin "1") (pinfunction "1_1") (pintype "passive"))
      (node (ref "IC2") (pin "10") (pinfunction "RHPOUT_10") (pintype "bidirectional"))
    )
    (net (code "40") (name "SWCLK") (class "Default")
      (node (ref "IC1") (pin "37") (pinfunction "PA14_37") (pintype "bidirectional"))
      (node (ref "JP2") (pin "1") (pinfunction "P$1_1") (pintype "bidirectional"))
    )
    (net (code "41") (name "SWDIO") (class "Default")
      (node (ref "IC1") (pin "34") (pinfunction "PA13_34") (pintype "bidirectional"))
      (node (ref "JP3") (pin "1") (pinfunction "P$1_1") (pintype "bidirectional"))
    )
    (net (code "42") (name "VDD") (class "Default")
      (node (ref "C1") (pin "1") (pinfunction "1_1") (pintype "bidirectional"))
      (node (ref "C11") (pin "2") (pinfunction "2_2") (pintype "passive"))
      (node (ref "C13") (pin "1") (pinfunction "1_1") (pintype "bidirectional"))
      (node (ref "C14") (pin "2") (pinfunction "2_2") (pintype "bidirectional"))
      (node (ref "C15") (pin "2") (pinfunction "2_2") (pintype "bidirectional"))
      (node (ref "C18") (pin "1") (pinfunction "C1_1") (pintype "bidirectional"))
      (node (ref "C33") (pin "1") (pinfunction "1_1") (pintype "bidirectional"))
      (node (ref "C5") (pin "2") (pinfunction "2_2") (pintype "bidirectional"))
      (node (ref "C6") (pin "1") (pinfunction "1_1") (pintype "bidirectional"))
      (node (ref "C8") (pin "1") (pinfunction "1_1") (pintype "bidirectional"))
      (node (ref "FB1") (pin "1") (pinfunction "1_1") (pintype "bidirectional"))
      (node (ref "IC1") (pin "1") (pinfunction "VBAT_1") (pintype "power_in"))
      (node (ref "IC1") (pin "24") (pinfunction "VDD_1_24") (pintype "power_in"))
      (node (ref "IC1") (pin "36") (pinfunction "VDD_2_36") (pintype "power_in"))
      (node (ref "IC1") (pin "48") (pinfunction "VDD_3_48") (pintype "power_in"))
      (node (ref "IC2") (pin "1") (pinfunction "DBVDD_1") (pintype "bidirectional"))
      (node (ref "IC2") (pin "27") (pinfunction "DCVDD_27") (pintype "bidirectional"))
      (node (ref "IC2") (pin "8") (pinfunction "HPVDD_8") (pintype "bidirectional"))
      (node (ref "JP4") (pin "1") (pinfunction "P$1_1") (pintype "bidirectional"))
      (node (ref "MK1") (pin "3") (pinfunction "VDD_3") (pintype "bidirectional"))
      (node (ref "R3") (pin "1") (pinfunction "1_1") (pintype "bidirectional"))
      (node (ref "R4") (pin "1") (pinfunction "1_1") (pintype "bidirectional"))
      (node (ref "R7") (pin "1") (pinfunction "1_1") (pintype "bidirectional"))
      (node (ref "S1") (pin "2") (pinfunction "NO_2") (pintype "bidirectional"))
      (node (ref "SW1") (pin "2") (pinfunction "2_2") (pintype "passive"))
      (node (ref "VREG-3V3") (pin "5") (pinfunction "OUT_5") (pintype "passive"))
    )
    (net (code "43") (name "unconnected-(IC1-PA0-Pad10)") (class "Default")
      (node (ref "IC1") (pin "10") (pinfunction "PA0_10") (pintype "bidirectional"))
    )
    (net (code "44") (name "unconnected-(IC1-PA6-Pad16)") (class "Default")
      (node (ref "IC1") (pin "16") (pinfunction "PA6_16") (pintype "bidirectional"))
    )
    (net (code "45") (name "unconnected-(IC1-PA7-Pad17)") (class "Default")
      (node (ref "IC1") (pin "17") (pinfunction "PA7_17") (pintype "bidirectional"))
    )
    (net (code "46") (name "unconnected-(IC1-PB0-Pad18)") (class "Default")
      (node (ref "IC1") (pin "18") (pinfunction "PB0_18") (pintype "bidirectional"))
    )
    (net (code "47") (name "unconnected-(IC1-PB1-Pad19)") (class "Default")
      (node (ref "IC1") (pin "19") (pinfunction "PB1_19") (pintype "bidirectional"))
    )
    (net (code "48") (name "unconnected-(IC1-PB4-Pad40)") (class "Default")
      (node (ref "IC1") (pin "40") (pinfunction "PB4_40") (pintype "bidirectional"))
    )
    (net (code "49") (name "unconnected-(IC1-PB14-Pad27)") (class "Default")
      (node (ref "IC1") (pin "27") (pinfunction "PB14_27") (pintype "bidirectional"))
    )
    (net (code "50") (name "unconnected-(IC1-PB15-Pad28)") (class "Default")
      (node (ref "IC1") (pin "28") (pinfunction "PB15_28") (pintype "bidirectional"))
    )
    (net (code "51") (name "unconnected-(IC1-PC13-Pad2)") (class "Default")
      (node (ref "IC1") (pin "2") (pinfunction "PC13_2") (pintype "bidirectional"))
    )
    (net (code "52") (name "unconnected-(IC1-PC14-OSC32_IN-Pad3)") (class "Default")
      (node (ref "IC1") (pin "3") (pinfunction "PC14-OSC32_IN_3") (pintype "bidirectional"))
    )
    (net (code "53") (name "unconnected-(IC1-PC15-OSC32_OUT-Pad4)") (class "Default")
      (node (ref "IC1") (pin "4") (pinfunction "PC15-OSC32_OUT_4") (pintype "bidirectional"))
    )
    (net (code "54") (name "unconnected-(IC2-ADCDAT-Pad6)") (class "Default")
      (node (ref "IC2") (pin "6") (pinfunction "ADCDAT_6") (pintype "bidirectional"))
    )
    (net (code "55") (name "unconnected-(IC2-ADCLRC-Pad7)") (class "Default")
      (node (ref "IC2") (pin "7") (pinfunction "ADCLRC_7") (pintype "bidirectional"))
    )
    (net (code "56") (name "unconnected-(IC2-CLKOUT-Pad2)") (class "Default")
      (node (ref "IC2") (pin "2") (pinfunction "CLKOUT_2") (pintype "bidirectional"))
    )
    (net (code "57") (name "unconnected-(IC2-LLINEIN-Pad20)") (class "Default")
      (node (ref "IC2") (pin "20") (pinfunction "LLINEIN_20") (pintype "bidirectional"))
    )
    (net (code "58") (name "unconnected-(IC2-MICBIAS-Pad17)") (class "Default")
      (node (ref "IC2") (pin "17") (pinfunction "MICBIAS_17") (pintype "bidirectional"))
    )
    (net (code "59") (name "unconnected-(IC2-MICIN-Pad18)") (class "Default")
      (node (ref "IC2") (pin "18") (pinfunction "MICIN_18") (pintype "bidirectional"))
    )
    (net (code "60") (name "unconnected-(IC2-RLINEIN-Pad19)") (class "Default")
      (node (ref "IC2") (pin "19") (pinfunction "RLINEIN_19") (pintype "bidirectional"))
    )
    (net (code "61") (name "unconnected-(IC2-XTO-Pad26)") (class "Default")
      (node (ref "IC2") (pin "26") (pinfunction "XTO_26") (pintype "bidirectional"))
    )
    (net (code "62") (name "unconnected-(J2-2_1-Pad2)") (class "Default")
      (node (ref "J2") (pin "2") (pinfunction "2_1_2") (pintype "bidirectional"))
    )
  )
)
